# YarnControl_Driver_v1_2.net
KiCad netlist of a schematic drawn in Altium Designer
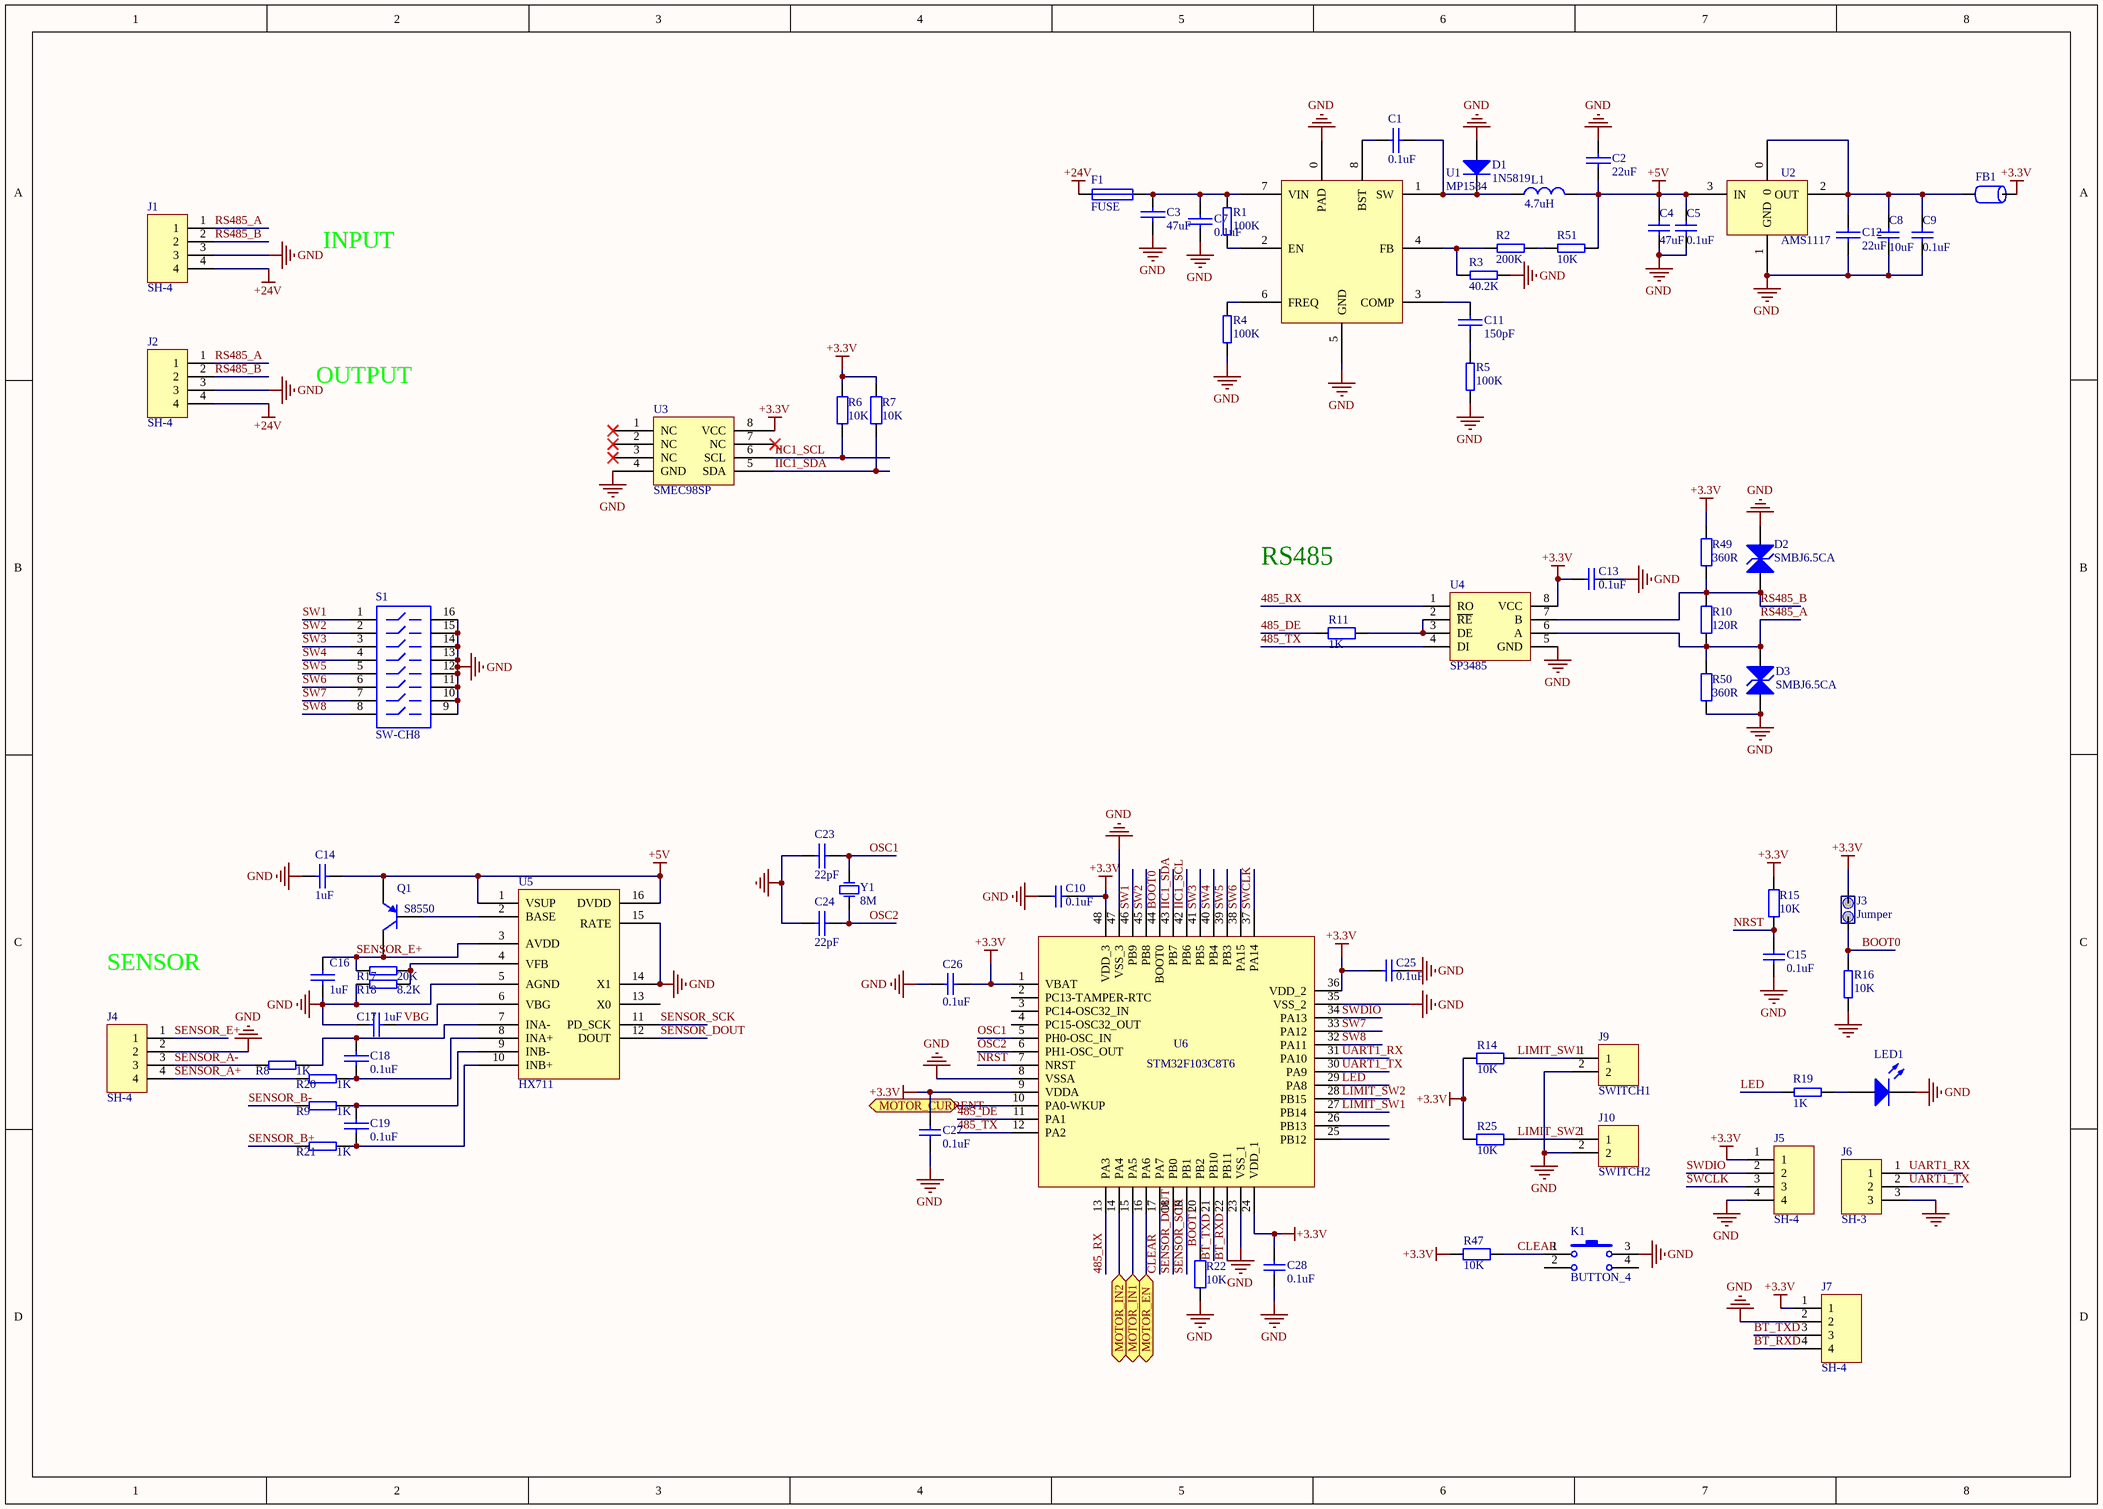
[diagram p0: YarnControl_Driver_v1.2.SchDoc]

(export (version "E")
  (design (tool "Eeschema 10.0.6"))
  (components
    (comp (ref "C1")
      (value "0.1uF")
      (footprint "0805")
      (description "电容")
      (libsource (lib "Component") (part "CAP"))
    )
    (comp (ref "C2")
      (value "22uF")
      (footprint "1206")
      (description "电容")
      (libsource (lib "Component") (part "CAP"))
    )
    (comp (ref "C3")
      (value "47uF")
      (footprint "1812")
      (description "电容")
      (libsource (lib "Component") (part "CAP"))
    )
    (comp (ref "C4") (value "47uF") (footprint "1210") (libsource (lib "Componet") (part "Cap0805")))
    (comp (ref "C5") (value "0.1uF") (footprint "0805") (libsource (lib "Componet") (part "Cap0805")))
    (comp (ref "C7")
      (value "0.1uF")
      (footprint "0805")
      (description "电容")
      (libsource (lib "Component") (part "CAP"))
    )
    (comp (ref "C8") (value "10uF") (footprint "0805") (libsource (lib "Componet") (part "Cap0805")))
    (comp (ref "C9") (value "0.1uF") (footprint "0805") (libsource (lib "Componet") (part "Cap0805")))
    (comp (ref "C10")
      (value "0.1uF")
      (footprint "0805")
      (description "Capacitor")
      (fields (field (name "PUBLISHER") "Altium Limited"))
      (libsource (lib "TIAN's Schlib") (part "Cap"))
    )
    (comp (ref "C11")
      (value "150pF")
      (footprint "0805")
      (description "电容")
      (libsource (lib "Component") (part "CAP"))
    )
    (comp (ref "C12")
      (value "22uF")
      (footprint "1206")
      (description "电容")
      (libsource (lib "Component") (part "CAP"))
    )
    (comp (ref "C13")
      (value "0.1uF")
      (footprint "0805")
      (description "Capacitor")
      (fields (field (name "PUBLISHER") "Altium Limited"))
      (libsource (lib "TIAN's Schlib") (part "Cap"))
    )
    (comp (ref "C14")
      (value "1uF")
      (footprint "0805")
      (description "电容")
      (libsource (lib "Component") (part "CAP"))
    )
    (comp (ref "C15")
      (value "0.1uF")
      (footprint "0805")
      (description "Capacitor")
      (fields (field (name "PUBLISHER") "Altium Limited"))
      (libsource (lib "TIAN's Schlib") (part "Cap"))
    )
    (comp (ref "C16")
      (value "1uF")
      (footprint "0805")
      (description "电容")
      (libsource (lib "Component") (part "CAP"))
    )
    (comp (ref "C17")
      (value "1uF")
      (footprint "0805")
      (description "电容")
      (libsource (lib "Component") (part "CAP"))
    )
    (comp (ref "C18")
      (value "0.1uF")
      (footprint "0805")
      (description "电容")
      (libsource (lib "Component") (part "CAP"))
    )
    (comp (ref "C19")
      (value "0.1uF")
      (footprint "0805")
      (description "电容")
      (libsource (lib "Component") (part "CAP"))
    )
    (comp (ref "C23")
      (value "22pF")
      (footprint "0805")
      (description "电容")
      (libsource (lib "Component") (part "CAP"))
    )
    (comp (ref "C24")
      (value "22pF")
      (footprint "0805")
      (description "电容")
      (libsource (lib "Component") (part "CAP"))
    )
    (comp (ref "C25")
      (value "0.1uF")
      (footprint "0805")
      (description "Capacitor")
      (fields (field (name "PUBLISHER") "Altium Limited"))
      (libsource (lib "TIAN's Schlib") (part "Cap"))
    )
    (comp (ref "C26")
      (value "0.1uF")
      (footprint "0805")
      (description "Capacitor")
      (fields (field (name "PUBLISHER") "Altium Limited"))
      (libsource (lib "TIAN's Schlib") (part "Cap"))
    )
    (comp (ref "C27")
      (value "0.1uF")
      (footprint "0805")
      (description "Capacitor")
      (fields (field (name "PUBLISHER") "Altium Limited"))
      (libsource (lib "TIAN's Schlib") (part "Cap"))
    )
    (comp (ref "C28")
      (value "0.1uF")
      (footprint "0805")
      (description "Capacitor")
      (fields (field (name "PUBLISHER") "Altium Limited"))
      (libsource (lib "TIAN's Schlib") (part "Cap"))
    )
    (comp (ref "D1")
      (value "1N5819")
      (footprint "Diode_TP2")
      (description "二极管")
      (fields (field (name "PUBLISHER") "Altium Limited"))
      (libsource (lib "Component") (part "Diode"))
    )
    (comp (ref "D2")
      (value "SMBJ6.5CA")
      (footprint "SMBJ_DO-214")
      (fields (field (name "PUBLISHER") "Altium Limited"))
      (libsource (lib "TIAN's Schlib") (part "TVS"))
    )
    (comp (ref "D3")
      (value "SMBJ6.5CA")
      (footprint "SMBJ_DO-214")
      (fields (field (name "PUBLISHER") "Altium Limited"))
      (libsource (lib "TIAN's Schlib") (part "TVS"))
    )
    (comp (ref "F1")
      (value "FUSE")
      (footprint "1206")
      (description "保险丝")
      (libsource (lib "Component") (part "FUSE"))
    )
    (comp (ref "FB1") (value "FERRITE") (footprint "0805") (libsource (lib "Connector") (part "FERRITE")))
    (comp (ref "J1") (value "SH-4") (footprint "J381-180") (libsource (lib "Connector") (part "SH-4")))
    (comp (ref "J2") (value "SH-4") (footprint "J381-180") (libsource (lib "Connector") (part "SH-4")))
    (comp (ref "J3") (value "Jumper") (footprint "J254-2") (libsource (lib "Connector") (part "Jumper")))
    (comp (ref "J4") (value "SH-4") (footprint "J381-180") (libsource (lib "Connector") (part "SH-4")))
    (comp (ref "J5") (value "SH-4") (footprint "J254-4") (libsource (lib "") (part "SH-4_1")))
    (comp (ref "J6") (value "SH-3") (footprint "J2.54-3") (libsource (lib "Connector") (part "SH-3")))
    (comp (ref "J7") (value "SH-4") (footprint "J254-4") (libsource (lib "") (part "SH-4_1")))
    (comp (ref "J9") (value "SWITCH1") (footprint "XH2.54-2T") (libsource (lib "Connector") (part "SH-2")))
    (comp (ref "J10") (value "SWITCH2") (footprint "XH2.54-2T") (libsource (lib "Connector") (part "SH-2")))
    (comp (ref "K1") (value "BUTTON_4") (footprint "Button1") (libsource (lib "Componet") (part "BUTTON_4")))
    (comp (ref "L1")
      (value "4.7uH")
      (footprint "Inductance6*6")
      (description "电感")
      (libsource (lib "Component") (part "Inductor"))
    )
    (comp (ref "LED1")
      (value "GREEN")
      (footprint "LED")
      (description "Typical RED, GREEN, YELLOW, AMBER GaAs LED")
      (fields (field (name "PUBLISHER") "Altium Limited"))
      (libsource (lib "Miscellaneous Devices") (part "LED2"))
    )
    (comp (ref "Q1") (value "S8550") (footprint "901X_SOT-23") (libsource (lib "Componet") (part "PNP")))
    (comp (ref "R1")
      (value "100K")
      (footprint "0805")
      (description "电阻")
      (libsource (lib "Component") (part "RES"))
    )
    (comp (ref "R2")
      (value "200K")
      (footprint "0805")
      (description "电阻")
      (libsource (lib "Component") (part "RES"))
    )
    (comp (ref "R3")
      (value "40.2K")
      (footprint "0805")
      (description "电阻")
      (libsource (lib "Component") (part "RES"))
    )
    (comp (ref "R4")
      (value "100K")
      (footprint "0805")
      (description "电阻")
      (libsource (lib "Component") (part "RES"))
    )
    (comp (ref "R5")
      (value "100K")
      (footprint "0805")
      (description "电阻")
      (libsource (lib "Component") (part "RES"))
    )
    (comp (ref "R6")
      (value "10K")
      (footprint "0805")
      (description "Resistor")
      (fields (field (name "PUBLISHER") "Altium Limited"))
      (libsource (lib "TIAN's Schlib") (part "Res2"))
    )
    (comp (ref "R7")
      (value "10K")
      (footprint "0805")
      (description "Resistor")
      (fields (field (name "PUBLISHER") "Altium Limited"))
      (libsource (lib "TIAN's Schlib") (part "Res2"))
    )
    (comp (ref "R8")
      (value "1K")
      (footprint "0805")
      (description "电阻")
      (libsource (lib "Component") (part "RES"))
    )
    (comp (ref "R9")
      (value "1K")
      (footprint "0805")
      (description "电阻")
      (libsource (lib "Component") (part "RES"))
    )
    (comp (ref "R10")
      (value "120R")
      (footprint "0805")
      (description "Resistor")
      (fields (field (name "PUBLISHER") "Altium Limited"))
      (libsource (lib "") (part "Res2_3"))
    )
    (comp (ref "R11")
      (value "1K")
      (footprint "0805")
      (description "Resistor")
      (fields (field (name "PUBLISHER") "Altium Limited"))
      (libsource (lib "") (part "Res2_1"))
    )
    (comp (ref "R14")
      (value "10K")
      (footprint "0805")
      (description "Resistor")
      (fields (field (name "PUBLISHER") "Altium Limited"))
      (libsource (lib "") (part "Res2_1"))
    )
    (comp (ref "R15")
      (value "10K")
      (footprint "0805")
      (description "Resistor")
      (fields (field (name "PUBLISHER") "Altium Limited"))
      (libsource (lib "TIAN's Schlib") (part "Res2"))
    )
    (comp (ref "R16")
      (value "10K")
      (footprint "0805")
      (description "电阻")
      (libsource (lib "Component") (part "RES"))
    )
    (comp (ref "R17")
      (value "20K")
      (footprint "0805")
      (description "电阻")
      (libsource (lib "Component") (part "RES"))
    )
    (comp (ref "R18")
      (value "8.2K")
      (footprint "0805")
      (description "电阻")
      (libsource (lib "Component") (part "RES"))
    )
    (comp (ref "R19")
      (value "1K")
      (footprint "0805")
      (description "电阻")
      (libsource (lib "Component") (part "RES"))
    )
    (comp (ref "R20")
      (value "1K")
      (footprint "0805")
      (description "电阻")
      (libsource (lib "Component") (part "RES"))
    )
    (comp (ref "R21")
      (value "1K")
      (footprint "0805")
      (description "电阻")
      (libsource (lib "Component") (part "RES"))
    )
    (comp (ref "R22")
      (value "10K")
      (footprint "0805")
      (description "Resistor")
      (fields (field (name "PUBLISHER") "Altium Limited"))
      (libsource (lib "TIAN's Schlib") (part "Res2"))
    )
    (comp (ref "R25")
      (value "10K")
      (footprint "0805")
      (description "Resistor")
      (fields (field (name "PUBLISHER") "Altium Limited"))
      (libsource (lib "") (part "Res2_2"))
    )
    (comp (ref "R47")
      (value "10K")
      (footprint "0805")
      (description "Resistor")
      (fields (field (name "PUBLISHER") "Altium Limited"))
      (libsource (lib "") (part "Res2_2"))
    )
    (comp (ref "R49")
      (value "360R")
      (footprint "0805")
      (description "Resistor")
      (fields (field (name "PUBLISHER") "Altium Limited"))
      (libsource (lib "") (part "Res2_2"))
    )
    (comp (ref "R50")
      (value "360R")
      (footprint "0805")
      (description "Resistor")
      (fields (field (name "PUBLISHER") "Altium Limited"))
      (libsource (lib "") (part "Res2_2"))
    )
    (comp (ref "R51")
      (value "10K")
      (footprint "0805")
      (description "电阻")
      (libsource (lib "Component") (part "RES"))
    )
    (comp (ref "S1")
      (value "SW-CH8")
      (footprint "SWITCH_8")
      (description "拨码开关CH8")
      (fields (field (name "PUBLISHER") "Altium Limited"))
      (libsource (lib "Component") (part "SW-CH8"))
    )
    (comp (ref "U1") (value "MP1584") (footprint "MP1584") (libsource (lib "Chip") (part "MP1584")))
    (comp (ref "U2") (value "AMS1117") (footprint "TO-223") (libsource (lib "Chip") (part "AMS1117")))
    (comp (ref "U3") (value "SMEC98SP") (footprint "SO-8") (libsource (lib "Chip") (part "SMEC98SP")))
    (comp (ref "U4")
      (value "SP3485")
      (footprint "SO-8")
      (description "485")
      (libsource (lib "TIAN's Schlib") (part "SP3485"))
    )
    (comp (ref "U5") (value "HX711") (footprint "SO-16") (libsource (lib "Chip") (part "HX711")))
    (comp (ref "U6")
      (value "STM32F103C8T6")
      (footprint "LQFP_48")
      (libsource (lib "Chip") (part "STM32F103C8T6"))
    )
    (comp (ref "Y1")
      (value "8M")
      (footprint "XTAL")
      (description "Crystal Oscillator")
      (fields (field (name "PUBLISHER") "Altium Limited"))
      (libsource (lib "MY Schlib") (part "XTAL"))
    )
  )
  (nets
    (net (code "1") (name "+3.3V") (class "Default")
      (node (ref "C10") (pin "1") (pinfunction "1_1") (pintype "passive"))
      (node (ref "C13") (pin "2") (pinfunction "2_2") (pintype "passive"))
      (node (ref "C25") (pin "2") (pinfunction "2_2") (pintype "passive"))
      (node (ref "C26") (pin "2") (pinfunction "2_2") (pintype "passive"))
      (node (ref "C27") (pin "2") (pinfunction "2_2") (pintype "passive"))
      (node (ref "C28") (pin "2") (pinfunction "2_2") (pintype "passive"))
      (node (ref "FB1") (pin "2") (pinfunction "2_2") (pintype "passive"))
      (node (ref "J3") (pin "2") (pinfunction "2_2") (pintype "passive"))
      (node (ref "J5") (pin "1") (pinfunction "1_1") (pintype "passive"))
      (node (ref "J7") (pin "1") (pinfunction "1_1") (pintype "passive"))
      (node (ref "R14") (pin "2") (pinfunction "2_2") (pintype "passive"))
      (node (ref "R15") (pin "2") (pinfunction "2_2") (pintype "passive"))
      (node (ref "R25") (pin "1") (pinfunction "1_1") (pintype "passive"))
      (node (ref "R47") (pin "1") (pinfunction "1_1") (pintype "passive"))
      (node (ref "R49") (pin "2") (pinfunction "2_2") (pintype "passive"))
      (node (ref "R6") (pin "2") (pinfunction "2_2") (pintype "passive"))
      (node (ref "R7") (pin "2") (pinfunction "2_2") (pintype "passive"))
      (node (ref "U3") (pin "8") (pinfunction "VCC_8") (pintype "passive"))
      (node (ref "U4") (pin "8") (pinfunction "VCC_8") (pintype "passive"))
      (node (ref "U6") (pin "1") (pinfunction "VBAT_1") (pintype "passive"))
      (node (ref "U6") (pin "24") (pinfunction "VDD_1_24") (pintype "passive"))
      (node (ref "U6") (pin "36") (pinfunction "VDD_2_36") (pintype "passive"))
      (node (ref "U6") (pin "48") (pinfunction "VDD_3_48") (pintype "passive"))
      (node (ref "U6") (pin "9") (pinfunction "VDDA_9") (pintype "passive"))
    )
    (net (code "2") (name "+5V") (class "Default")
      (node (ref "C14") (pin "2") (pinfunction "2_2") (pintype "passive"))
      (node (ref "C2") (pin "2") (pinfunction "2_2") (pintype "passive"))
      (node (ref "C4") (pin "2") (pinfunction "2_2") (pintype "passive"))
      (node (ref "C5") (pin "2") (pinfunction "2_2") (pintype "passive"))
      (node (ref "L1") (pin "2") (pinfunction "2_2") (pintype "passive"))
      (node (ref "Q1") (pin "3") (pinfunction "E_3") (pintype "passive"))
      (node (ref "R51") (pin "1") (pinfunction "1_1") (pintype "passive"))
      (node (ref "U2") (pin "3") (pinfunction "IN_3") (pintype "passive"))
      (node (ref "U5") (pin "1") (pinfunction "VSUP_1") (pintype "passive"))
      (node (ref "U5") (pin "16") (pinfunction "DVDD_16") (pintype "passive"))
    )
    (net (code "3") (name "+24V") (class "Default")
      (node (ref "F1") (pin "1") (pinfunction "1_1") (pintype "passive"))
      (node (ref "J1") (pin "4") (pinfunction "4_4") (pintype "passive"))
      (node (ref "J2") (pin "4") (pinfunction "4_4") (pintype "passive"))
    )
    (net (code "4") (name "/485_DE") (class "Default")
      (node (ref "R11") (pin "2") (pinfunction "2_2") (pintype "passive"))
      (node (ref "U6") (pin "11") (pinfunction "PA1_11") (pintype "passive"))
    )
    (net (code "5") (name "/485_RX") (class "Default")
      (node (ref "U4") (pin "1") (pinfunction "RO_1") (pintype "passive"))
      (node (ref "U6") (pin "13") (pinfunction "PA3_13") (pintype "passive"))
    )
    (net (code "6") (name "/485_TX") (class "Default")
      (node (ref "U4") (pin "4") (pinfunction "DI_4") (pintype "passive"))
      (node (ref "U6") (pin "12") (pinfunction "PA2_12") (pintype "passive"))
    )
    (net (code "7") (name "/BOOT0") (class "Default")
      (node (ref "J3") (pin "1") (pinfunction "1_1") (pintype "passive"))
      (node (ref "R16") (pin "1") (pinfunction "1_1") (pintype "passive"))
      (node (ref "U6") (pin "44") (pinfunction "BOOT0_44") (pintype "passive"))
    )
    (net (code "8") (name "/BOOT1") (class "Default")
      (node (ref "R22") (pin "2") (pinfunction "2_2") (pintype "passive"))
      (node (ref "U6") (pin "20") (pinfunction "PB2_20") (pintype "passive"))
    )
    (net (code "9") (name "/BT_RXD") (class "Default")
      (node (ref "J7") (pin "4") (pinfunction "4_4") (pintype "passive"))
      (node (ref "U6") (pin "22") (pinfunction "PB11_22") (pintype "passive"))
    )
    (net (code "10") (name "/BT_TXD") (class "Default")
      (node (ref "J7") (pin "3") (pinfunction "3_3") (pintype "passive"))
      (node (ref "U6") (pin "21") (pinfunction "PB10_21") (pintype "passive"))
    )
    (net (code "11") (name "/CLEAR") (class "Default")
      (node (ref "K1") (pin "1") (pinfunction "1_1") (pintype "passive"))
      (node (ref "R47") (pin "2") (pinfunction "2_2") (pintype "passive"))
      (node (ref "U6") (pin "17") (pinfunction "PA7_17") (pintype "passive"))
    )
    (net (code "12") (name "/IIC1_SCL") (class "Default")
      (node (ref "R6") (pin "1") (pinfunction "1_1") (pintype "passive"))
      (node (ref "U3") (pin "6") (pinfunction "SCL_6") (pintype "passive"))
      (node (ref "U6") (pin "42") (pinfunction "PB6_42") (pintype "passive"))
    )
    (net (code "13") (name "/IIC1_SDA") (class "Default")
      (node (ref "R7") (pin "1") (pinfunction "1_1") (pintype "passive"))
      (node (ref "U3") (pin "5") (pinfunction "SDA_5") (pintype "passive"))
      (node (ref "U6") (pin "43") (pinfunction "PB7_43") (pintype "passive"))
    )
    (net (code "14") (name "/LED") (class "Default")
      (node (ref "R19") (pin "2") (pinfunction "2_2") (pintype "passive"))
      (node (ref "U6") (pin "29") (pinfunction "PA8_29") (pintype "passive"))
    )
    (net (code "15") (name "/LIMIT_SW1") (class "Default")
      (node (ref "J9") (pin "1") (pinfunction "1_1") (pintype "passive"))
      (node (ref "R14") (pin "1") (pinfunction "1_1") (pintype "passive"))
      (node (ref "U6") (pin "27") (pinfunction "PB14_27") (pintype "passive"))
    )
    (net (code "16") (name "/LIMIT_SW2") (class "Default")
      (node (ref "J10") (pin "1") (pinfunction "1_1") (pintype "passive"))
      (node (ref "R25") (pin "2") (pinfunction "2_2") (pintype "passive"))
      (node (ref "U6") (pin "28") (pinfunction "PB15_28") (pintype "passive"))
    )
    (net (code "17") (name "/MOTOR_CURRENT") (class "Default")
      (node (ref "U6") (pin "10") (pinfunction "PA0-WKUP_10") (pintype "passive"))
    )
    (net (code "18") (name "/MOTOR_EN") (class "Default")
      (node (ref "U6") (pin "16") (pinfunction "PA6_16") (pintype "passive"))
    )
    (net (code "19") (name "/MOTOR_IN1") (class "Default")
      (node (ref "U6") (pin "15") (pinfunction "PA5_15") (pintype "passive"))
    )
    (net (code "20") (name "/MOTOR_IN2") (class "Default")
      (node (ref "U6") (pin "14") (pinfunction "PA4_14") (pintype "passive"))
    )
    (net (code "21") (name "/NRST") (class "Default")
      (node (ref "C15") (pin "2") (pinfunction "2_2") (pintype "passive"))
      (node (ref "R15") (pin "1") (pinfunction "1_1") (pintype "passive"))
      (node (ref "U6") (pin "7") (pinfunction "NRST_7") (pintype "passive"))
    )
    (net (code "22") (name "/OSC1") (class "Default")
      (node (ref "C23") (pin "2") (pinfunction "2_2") (pintype "passive"))
      (node (ref "U6") (pin "5") (pinfunction "PH0-OSC_IN_5") (pintype "passive"))
      (node (ref "Y1") (pin "2") (pinfunction "OSC2_2") (pintype "passive"))
    )
    (net (code "23") (name "/OSC2") (class "Default")
      (node (ref "C24") (pin "2") (pinfunction "2_2") (pintype "passive"))
      (node (ref "U6") (pin "6") (pinfunction "PH1-OSC_OUT_6") (pintype "passive"))
      (node (ref "Y1") (pin "1") (pinfunction "OSC1_1") (pintype "passive"))
    )
    (net (code "24") (name "/RS485_A") (class "Default")
      (node (ref "D3") (pin "2") (pinfunction "K_2") (pintype "passive"))
      (node (ref "J1") (pin "1") (pinfunction "1_1") (pintype "passive"))
      (node (ref "J2") (pin "1") (pinfunction "1_1") (pintype "passive"))
      (node (ref "R10") (pin "2") (pinfunction "2_2") (pintype "passive"))
      (node (ref "R50") (pin "2") (pinfunction "2_2") (pintype "passive"))
      (node (ref "U4") (pin "6") (pinfunction "A_6") (pintype "passive"))
    )
    (net (code "25") (name "/RS485_B") (class "Default")
      (node (ref "D2") (pin "1") (pinfunction "A_1") (pintype "passive"))
      (node (ref "J1") (pin "2") (pinfunction "2_2") (pintype "passive"))
      (node (ref "J2") (pin "2") (pinfunction "2_2") (pintype "passive"))
      (node (ref "R10") (pin "1") (pinfunction "1_1") (pintype "passive"))
      (node (ref "R49") (pin "1") (pinfunction "1_1") (pintype "passive"))
      (node (ref "U4") (pin "7") (pinfunction "B_7") (pintype "passive"))
    )
    (net (code "26") (name "/SENSOR_A+") (class "Default")
      (node (ref "J4") (pin "4") (pinfunction "4_4") (pintype "passive"))
      (node (ref "R20") (pin "2") (pinfunction "2_2") (pintype "passive"))
    )
    (net (code "27") (name "/SENSOR_A-") (class "Default")
      (node (ref "J4") (pin "3") (pinfunction "3_3") (pintype "passive"))
      (node (ref "R8") (pin "2") (pinfunction "2_2") (pintype "passive"))
    )
    (net (code "28") (name "/SENSOR_B+") (class "Default")
      (node (ref "R21") (pin "2") (pinfunction "2_2") (pintype "passive"))
    )
    (net (code "29") (name "/SENSOR_B-") (class "Default")
      (node (ref "R9") (pin "2") (pinfunction "2_2") (pintype "passive"))
    )
    (net (code "30") (name "/SENSOR_DOUT") (class "Default")
      (node (ref "U5") (pin "12") (pinfunction "DOUT_12") (pintype "passive"))
      (node (ref "U6") (pin "18") (pinfunction "PB0_18") (pintype "passive"))
    )
    (net (code "31") (name "/SENSOR_E+") (class "Default")
      (node (ref "C16") (pin "2") (pinfunction "2_2") (pintype "passive"))
      (node (ref "J4") (pin "1") (pinfunction "1_1") (pintype "passive"))
      (node (ref "Q1") (pin "1") (pinfunction "C_1") (pintype "passive"))
      (node (ref "R17") (pin "2") (pinfunction "2_2") (pintype "passive"))
      (node (ref "U5") (pin "3") (pinfunction "AVDD_3") (pintype "passive"))
    )
    (net (code "32") (name "/SENSOR_SCK") (class "Default")
      (node (ref "U5") (pin "11") (pinfunction "PD_SCK_11") (pintype "passive"))
      (node (ref "U6") (pin "19") (pinfunction "PB1_19") (pintype "passive"))
    )
    (net (code "33") (name "/SW1") (class "Default")
      (node (ref "S1") (pin "1") (pinfunction "1_1") (pintype "passive"))
      (node (ref "U6") (pin "46") (pinfunction "PB9_46") (pintype "passive"))
    )
    (net (code "34") (name "/SW2") (class "Default")
      (node (ref "S1") (pin "2") (pinfunction "2_2") (pintype "passive"))
      (node (ref "U6") (pin "45") (pinfunction "PB8_45") (pintype "passive"))
    )
    (net (code "35") (name "/SW3") (class "Default")
      (node (ref "S1") (pin "3") (pinfunction "3_3") (pintype "passive"))
      (node (ref "U6") (pin "41") (pinfunction "PB5_41") (pintype "passive"))
    )
    (net (code "36") (name "/SW4") (class "Default")
      (node (ref "S1") (pin "4") (pinfunction "4_4") (pintype "passive"))
      (node (ref "U6") (pin "40") (pinfunction "PB4_40") (pintype "passive"))
    )
    (net (code "37") (name "/SW5") (class "Default")
      (node (ref "S1") (pin "5") (pinfunction "5_5") (pintype "passive"))
      (node (ref "U6") (pin "39") (pinfunction "PB3_39") (pintype "passive"))
    )
    (net (code "38") (name "/SW6") (class "Default")
      (node (ref "S1") (pin "6") (pinfunction "6_6") (pintype "passive"))
      (node (ref "U6") (pin "38") (pinfunction "PA15_38") (pintype "passive"))
    )
    (net (code "39") (name "/SW7") (class "Default")
      (node (ref "S1") (pin "7") (pinfunction "7_7") (pintype "passive"))
      (node (ref "U6") (pin "33") (pinfunction "PA12_33") (pintype "passive"))
    )
    (net (code "40") (name "/SW8") (class "Default")
      (node (ref "S1") (pin "8") (pinfunction "8_8") (pintype "passive"))
      (node (ref "U6") (pin "32") (pinfunction "PA11_32") (pintype "passive"))
    )
    (net (code "41") (name "/SWCLK") (class "Default")
      (node (ref "J5") (pin "3") (pinfunction "3_3") (pintype "passive"))
      (node (ref "U6") (pin "37") (pinfunction "PA14_37") (pintype "passive"))
    )
    (net (code "42") (name "/SWDIO") (class "Default")
      (node (ref "J5") (pin "2") (pinfunction "2_2") (pintype "passive"))
      (node (ref "U6") (pin "34") (pinfunction "PA13_34") (pintype "passive"))
    )
    (net (code "43") (name "/UART1_RX") (class "Default")
      (node (ref "J6") (pin "1") (pinfunction "1_1") (pintype "passive"))
      (node (ref "U6") (pin "31") (pinfunction "PA10_31") (pintype "passive"))
    )
    (net (code "44") (name "/UART1_TX") (class "Default")
      (node (ref "J6") (pin "2") (pinfunction "2_2") (pintype "passive"))
      (node (ref "U6") (pin "30") (pinfunction "PA9_30") (pintype "passive"))
    )
    (net (code "45") (name "/VBG") (class "Default")
      (node (ref "C17") (pin "1") (pinfunction "1_1") (pintype "passive"))
      (node (ref "U5") (pin "6") (pinfunction "VBG_6") (pintype "passive"))
    )
    (net (code "46") (name "GND") (class "Default")
      (node (ref "C10") (pin "2") (pinfunction "2_2") (pintype "passive"))
      (node (ref "C12") (pin "2") (pinfunction "2_2") (pintype "passive"))
      (node (ref "C13") (pin "1") (pinfunction "1_1") (pintype "passive"))
      (node (ref "C14") (pin "1") (pinfunction "1_1") (pintype "passive"))
      (node (ref "C15") (pin "1") (pinfunction "1_1") (pintype "passive"))
      (node (ref "C16") (pin "1") (pinfunction "1_1") (pintype "passive"))
      (node (ref "C17") (pin "2") (pinfunction "2_2") (pintype "passive"))
      (node (ref "C2") (pin "1") (pinfunction "1_1") (pintype "passive"))
      (node (ref "C23") (pin "1") (pinfunction "1_1") (pintype "passive"))
      (node (ref "C24") (pin "1") (pinfunction "1_1") (pintype "passive"))
      (node (ref "C25") (pin "1") (pinfunction "1_1") (pintype "passive"))
      (node (ref "C26") (pin "1") (pinfunction "1_1") (pintype "passive"))
      (node (ref "C27") (pin "1") (pinfunction "1_1") (pintype "passive"))
      (node (ref "C28") (pin "1") (pinfunction "1_1") (pintype "passive"))
      (node (ref "C3") (pin "2") (pinfunction "2_2") (pintype "passive"))
      (node (ref "C4") (pin "1") (pinfunction "1_1") (pintype "passive"))
      (node (ref "C5") (pin "1") (pinfunction "1_1") (pintype "passive"))
      (node (ref "C7") (pin "2") (pinfunction "2_2") (pintype "passive"))
      (node (ref "C8") (pin "1") (pinfunction "1_1") (pintype "passive"))
      (node (ref "C9") (pin "1") (pinfunction "1_1") (pintype "passive"))
      (node (ref "D1") (pin "1") (pinfunction "A_1") (pintype "passive"))
      (node (ref "D2") (pin "2") (pinfunction "K_2") (pintype "passive"))
      (node (ref "D3") (pin "1") (pinfunction "A_1") (pintype "passive"))
      (node (ref "J1") (pin "3") (pinfunction "3_3") (pintype "passive"))
      (node (ref "J10") (pin "2") (pinfunction "2_2") (pintype "passive"))
      (node (ref "J2") (pin "3") (pinfunction "3_3") (pintype "passive"))
      (node (ref "J4") (pin "2") (pinfunction "2_2") (pintype "passive"))
      (node (ref "J5") (pin "4") (pinfunction "4_4") (pintype "passive"))
      (node (ref "J6") (pin "3") (pinfunction "3_3") (pintype "passive"))
      (node (ref "J7") (pin "2") (pinfunction "2_2") (pintype "passive"))
      (node (ref "J9") (pin "2") (pinfunction "2_2") (pintype "passive"))
      (node (ref "K1") (pin "3") (pinfunction "3_3") (pintype "passive"))
      (node (ref "LED1") (pin "2") (pinfunction "K_2") (pintype "passive"))
      (node (ref "R16") (pin "2") (pinfunction "2_2") (pintype "passive"))
      (node (ref "R18") (pin "2") (pinfunction "2_2") (pintype "passive"))
      (node (ref "R22") (pin "1") (pinfunction "1_1") (pintype "passive"))
      (node (ref "R3") (pin "1") (pinfunction "1_1") (pintype "passive"))
      (node (ref "R4") (pin "1") (pinfunction "1_1") (pintype "passive"))
      (node (ref "R5") (pin "1") (pinfunction "1_1") (pintype "passive"))
      (node (ref "R50") (pin "1") (pinfunction "1_1") (pintype "passive"))
      (node (ref "S1") (pin "10") (pinfunction "10_10") (pintype "passive"))
      (node (ref "S1") (pin "11") (pinfunction "11_11") (pintype "passive"))
      (node (ref "S1") (pin "12") (pinfunction "12_12") (pintype "passive"))
      (node (ref "S1") (pin "13") (pinfunction "13_13") (pintype "passive"))
      (node (ref "S1") (pin "14") (pinfunction "14_14") (pintype "passive"))
      (node (ref "S1") (pin "15") (pinfunction "15_15") (pintype "passive"))
      (node (ref "S1") (pin "16") (pinfunction "16_16") (pintype "passive"))
      (node (ref "S1") (pin "9") (pinfunction "9_9") (pintype "passive"))
      (node (ref "U1") (pin "0") (pinfunction "PAD_0") (pintype "passive"))
      (node (ref "U1") (pin "5") (pinfunction "GND_5") (pintype "passive"))
      (node (ref "U2") (pin "1") (pinfunction "GND_1") (pintype "passive"))
      (node (ref "U3") (pin "4") (pinfunction "GND_4") (pintype "passive"))
      (node (ref "U4") (pin "5") (pinfunction "GND_5") (pintype "passive"))
      (node (ref "U5") (pin "14") (pinfunction "X1_14") (pintype "passive"))
      (node (ref "U5") (pin "15") (pinfunction "RATE_15") (pintype "passive"))
      (node (ref "U5") (pin "5") (pinfunction "AGND_5") (pintype "passive"))
      (node (ref "U6") (pin "23") (pinfunction "VSS_1_23") (pintype "passive"))
      (node (ref "U6") (pin "35") (pinfunction "VSS_2_35") (pintype "passive"))
      (node (ref "U6") (pin "47") (pinfunction "VSS_3_47") (pintype "passive"))
      (node (ref "U6") (pin "8") (pinfunction "VSSA_8") (pintype "passive"))
    )
    (net (code "47") (name "Net-(C11-Pad2)") (class "Default")
      (node (ref "C11") (pin "2") (pinfunction "2_2") (pintype "passive"))
      (node (ref "R5") (pin "2") (pinfunction "2_2") (pintype "passive"))
    )
    (net (code "48") (name "Net-(D1-K)") (class "Default")
      (node (ref "C1") (pin "2") (pinfunction "2_2") (pintype "passive"))
      (node (ref "D1") (pin "2") (pinfunction "K_2") (pintype "passive"))
      (node (ref "L1") (pin "1") (pinfunction "1_1") (pintype "passive"))
      (node (ref "U1") (pin "1") (pinfunction "SW_1") (pintype "passive"))
    )
    (net (code "49") (name "Net-(LED1-A)") (class "Default")
      (node (ref "LED1") (pin "1") (pinfunction "A_1") (pintype "passive"))
      (node (ref "R19") (pin "1") (pinfunction "1_1") (pintype "passive"))
    )
    (net (code "50") (name "Net-(Q1-B)") (class "Default")
      (node (ref "Q1") (pin "2") (pinfunction "B_2") (pintype "passive"))
      (node (ref "U5") (pin "2") (pinfunction "BASE_2") (pintype "passive"))
    )
    (net (code "51") (name "Net-(R2-Pad1)") (class "Default")
      (node (ref "R2") (pin "1") (pinfunction "1_1") (pintype "passive"))
      (node (ref "R51") (pin "2") (pinfunction "2_2") (pintype "passive"))
    )
    (net (code "52") (name "Net-(U1-BST)") (class "Default")
      (node (ref "C1") (pin "1") (pinfunction "1_1") (pintype "passive"))
      (node (ref "U1") (pin "8") (pinfunction "BST_8") (pintype "passive"))
    )
    (net (code "53") (name "Net-(U1-COMP)") (class "Default")
      (node (ref "C11") (pin "1") (pinfunction "1_1") (pintype "passive"))
      (node (ref "U1") (pin "3") (pinfunction "COMP_3") (pintype "passive"))
    )
    (net (code "54") (name "Net-(U1-EN)") (class "Default")
      (node (ref "R1") (pin "1") (pinfunction "1_1") (pintype "passive"))
      (node (ref "U1") (pin "2") (pinfunction "EN_2") (pintype "passive"))
    )
    (net (code "55") (name "Net-(U1-FB)") (class "Default")
      (node (ref "R2") (pin "2") (pinfunction "2_2") (pintype "passive"))
      (node (ref "R3") (pin "2") (pinfunction "2_2") (pintype "passive"))
      (node (ref "U1") (pin "4") (pinfunction "FB_4") (pintype "passive"))
    )
    (net (code "56") (name "Net-(U1-FREQ)") (class "Default")
      (node (ref "R4") (pin "2") (pinfunction "2_2") (pintype "passive"))
      (node (ref "U1") (pin "6") (pinfunction "FREQ_6") (pintype "passive"))
    )
    (net (code "57") (name "Net-(U1-VIN)") (class "Default")
      (node (ref "C3") (pin "1") (pinfunction "1_1") (pintype "passive"))
      (node (ref "C7") (pin "1") (pinfunction "1_1") (pintype "passive"))
      (node (ref "F1") (pin "2") (pinfunction "2_2") (pintype "passive"))
      (node (ref "R1") (pin "2") (pinfunction "2_2") (pintype "passive"))
      (node (ref "U1") (pin "7") (pinfunction "VIN_7") (pintype "passive"))
    )
    (net (code "58") (name "Net-(U2-OUT)") (class "Default")
      (node (ref "C12") (pin "1") (pinfunction "1_1") (pintype "passive"))
      (node (ref "C8") (pin "2") (pinfunction "2_2") (pintype "passive"))
      (node (ref "C9") (pin "2") (pinfunction "2_2") (pintype "passive"))
      (node (ref "FB1") (pin "1") (pinfunction "1_1") (pintype "passive"))
      (node (ref "U2") (pin "0") (pinfunction "0_0") (pintype "passive"))
      (node (ref "U2") (pin "2") (pinfunction "OUT_2") (pintype "passive"))
    )
    (net (code "59") (name "Net-(U4-DE)") (class "Default")
      (node (ref "R11") (pin "1") (pinfunction "1_1") (pintype "passive"))
      (node (ref "U4") (pin "2") (pinfunction "~{RE}_2") (pintype "passive"))
      (node (ref "U4") (pin "3") (pinfunction "DE_3") (pintype "passive"))
    )
    (net (code "60") (name "Net-(U5-INA+)") (class "Default")
      (node (ref "C18") (pin "2") (pinfunction "2_2") (pintype "passive"))
      (node (ref "R20") (pin "1") (pinfunction "1_1") (pintype "passive"))
      (node (ref "U5") (pin "8") (pinfunction "INA+_8") (pintype "passive"))
    )
    (net (code "61") (name "Net-(U5-INA-)") (class "Default")
      (node (ref "C18") (pin "1") (pinfunction "1_1") (pintype "passive"))
      (node (ref "R8") (pin "1") (pinfunction "1_1") (pintype "passive"))
      (node (ref "U5") (pin "7") (pinfunction "INA-_7") (pintype "passive"))
    )
    (net (code "62") (name "Net-(U5-INB+)") (class "Default")
      (node (ref "C19") (pin "2") (pinfunction "2_2") (pintype "passive"))
      (node (ref "R21") (pin "1") (pinfunction "1_1") (pintype "passive"))
      (node (ref "U5") (pin "10") (pinfunction "INB+_10") (pintype "passive"))
    )
    (net (code "63") (name "Net-(U5-INB-)") (class "Default")
      (node (ref "C19") (pin "1") (pinfunction "1_1") (pintype "passive"))
      (node (ref "R9") (pin "1") (pinfunction "1_1") (pintype "passive"))
      (node (ref "U5") (pin "9") (pinfunction "INB-_9") (pintype "passive"))
    )
    (net (code "64") (name "Net-(U5-VFB)") (class "Default")
      (node (ref "R17") (pin "1") (pinfunction "1_1") (pintype "passive"))
      (node (ref "R18") (pin "1") (pinfunction "1_1") (pintype "passive"))
      (node (ref "U5") (pin "4") (pinfunction "VFB_4") (pintype "passive"))
    )
    (net (code "65") (name "unconnected-(K1-Pad2)") (class "Default")
      (node (ref "K1") (pin "2") (pinfunction "2_2") (pintype "passive"))
    )
    (net (code "66") (name "unconnected-(K1-Pad4)") (class "Default")
      (node (ref "K1") (pin "4") (pinfunction "4_4") (pintype "passive"))
    )
    (net (code "67") (name "unconnected-(U3-NC-Pad1)") (class "Default")
      (node (ref "U3") (pin "1") (pinfunction "NC_1") (pintype "passive+no_connect"))
    )
    (net (code "68") (name "unconnected-(U3-NC-Pad2)") (class "Default")
      (node (ref "U3") (pin "2") (pinfunction "NC_2") (pintype "passive+no_connect"))
    )
    (net (code "69") (name "unconnected-(U3-NC-Pad3)") (class "Default")
      (node (ref "U3") (pin "3") (pinfunction "NC_3") (pintype "passive+no_connect"))
    )
    (net (code "70") (name "unconnected-(U3-NC-Pad7)") (class "Default")
      (node (ref "U3") (pin "7") (pinfunction "NC_7") (pintype "passive+no_connect"))
    )
    (net (code "71") (name "unconnected-(U5-X0-Pad13)") (class "Default")
      (node (ref "U5") (pin "13") (pinfunction "X0_13") (pintype "passive"))
    )
    (net (code "72") (name "unconnected-(U6-PB12-Pad25)") (class "Default")
      (node (ref "U6") (pin "25") (pinfunction "PB12_25") (pintype "passive"))
    )
    (net (code "73") (name "unconnected-(U6-PB13-Pad26)") (class "Default")
      (node (ref "U6") (pin "26") (pinfunction "PB13_26") (pintype "passive"))
    )
    (net (code "74") (name "unconnected-(U6-PC13-TAMPER-RTC-Pad2)") (class "Default")
      (node (ref "U6") (pin "2") (pinfunction "PC13-TAMPER-RTC_2") (pintype "passive"))
    )
    (net (code "75") (name "unconnected-(U6-PC14-OSC32_IN-Pad3)") (class "Default")
      (node (ref "U6") (pin "3") (pinfunction "PC14-OSC32_IN_3") (pintype "passive"))
    )
    (net (code "76") (name "unconnected-(U6-PC15-OSC32_OUT-Pad4)") (class "Default")
      (node (ref "U6") (pin "4") (pinfunction "PC15-OSC32_OUT_4") (pintype "passive"))
    )
  )
)
